# power_management.net
KiCad netlist of a schematic drawn in Altium Designer
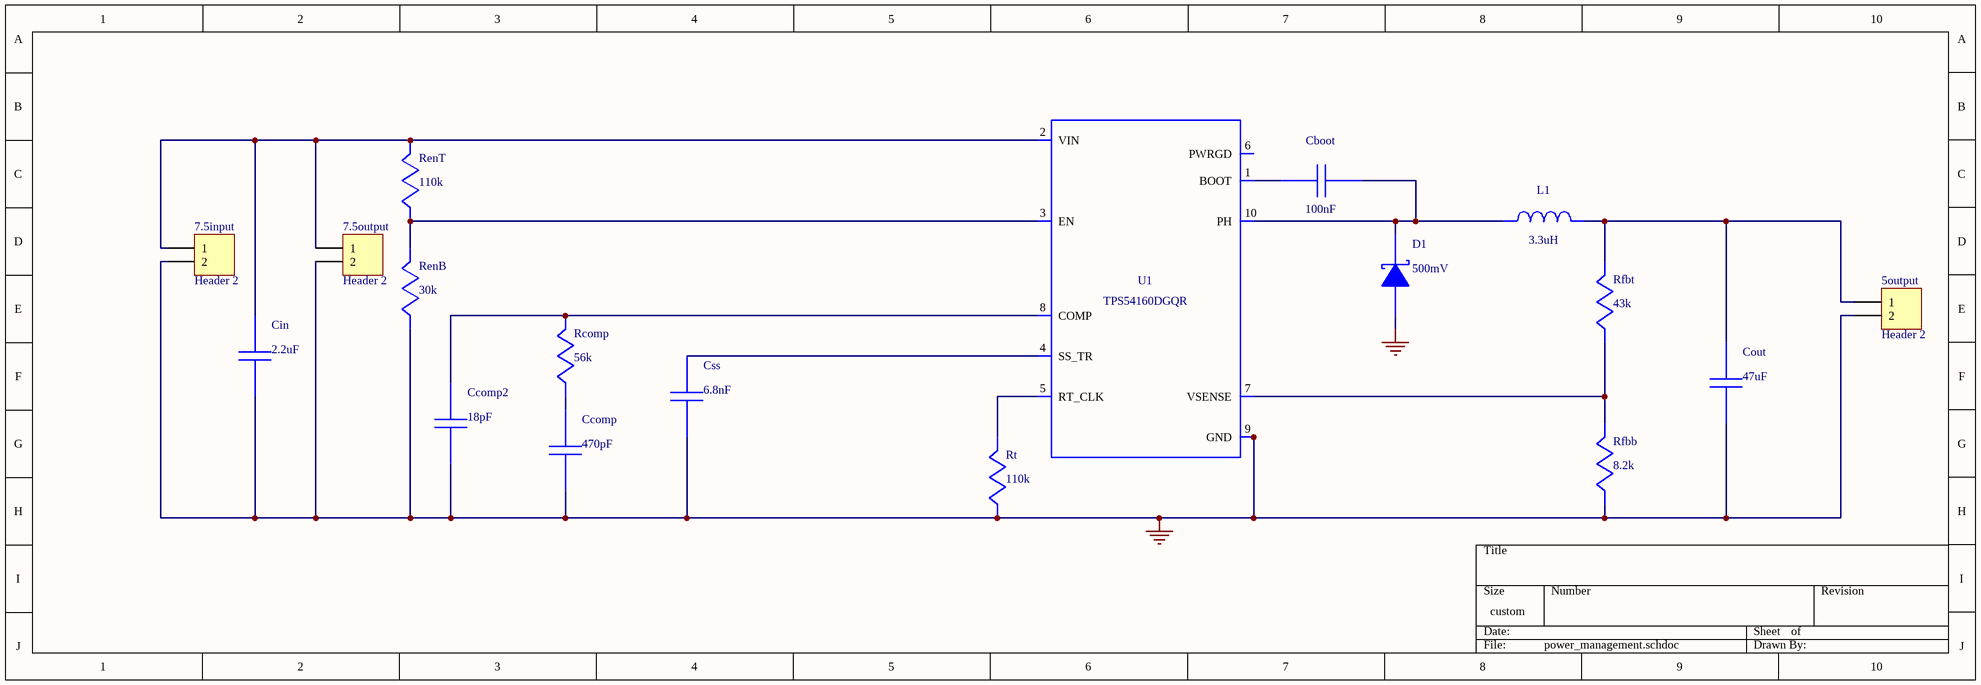
[diagram p0: power_management.schdoc]

(export (version "E")
  (design (tool "Eeschema 10.0.6"))
  (components
    (comp (ref "5output")
      (value "Header 2")
      (footprint "HDR1X2")
      (description "Header, 2-Pin")
      (fields (field (name "PUBLISHER") "Altium Limited"))
      (libsource (lib "Miscellaneous Connectors") (part "Header 2"))
    )
    (comp (ref "7.5input")
      (value "Header 2")
      (footprint "HDR1X2")
      (description "Header, 2-Pin")
      (fields (field (name "PUBLISHER") "Altium Limited"))
      (libsource (lib "Miscellaneous Connectors") (part "Header 2"))
    )
    (comp (ref "7.5output")
      (value "Header 2")
      (footprint "HDR1X2")
      (description "Header, 2-Pin")
      (fields (field (name "PUBLISHER") "Altium Limited"))
      (libsource (lib "Miscellaneous Connectors") (part "Header 2"))
    )
    (comp (ref "Cboot")
      (value "100nF")
      (footprint "RAD-0.2")
      (description "GRM155R61A104KA0")
      (fields (field (name "MANUFACTURER PART NUMBER") "GRM155R61A104KA01D"))
      (libsource (lib "TI WEBENCH") (part "Cboot"))
    )
    (comp (ref "Ccomp")
      (value "470pF")
      (footprint "RAD-0.2")
      (description "CC0805KRX7R9BB47")
      (fields (field (name "MANUFACTURER PART NUMBER") "CC0805KRX7R9BB471"))
      (libsource (lib "TI WEBENCH") (part "Ccomp"))
    )
    (comp (ref "Ccomp2")
      (value "18pF")
      (footprint "RAD-0.1")
      (description "C0805C180K5GACTU")
      (libsource (lib "TI WEBENCH") (part "Ccomp2"))
    )
    (comp (ref "Cin")
      (value "2.2uF")
      (footprint "CAPR5-4X5")
      (description "GRM188R61A225KE3")
      (fields (field (name "MANUFACTURER PART NUMBER") "GRM188R61A225KE34D"))
      (libsource (lib "TI WEBENCH") (part "Cin"))
    )
    (comp (ref "Cout")
      (value "47uF")
      (footprint "CAPR5-4X5")
      (description "C2012X5R1A476M12")
      (fields (field (name "MANUFACTURER PART NUMBER") "C2012X5R1A476M125AC"))
      (libsource (lib "TI WEBENCH") (part "Cout"))
    )
    (comp (ref "Css")
      (value "6.8nF")
      (footprint "RAD-0.1")
      (description "CC0805KRX7R9BB68")
      (fields (field (name "MANUFACTURER PART NUMBER") "CC0805KRX7R9BB682"))
      (libsource (lib "TI WEBENCH") (part "Css"))
    )
    (comp (ref "D1")
      (value "500mV")
      (footprint "DIODE-0.7")
      (description "B340A-13-F")
      (libsource (lib "TI WEBENCH") (part "D1"))
    )
    (comp (ref "L1")
      (value "3.3uH")
      (footprint "AXIAL-0.4")
      (description "SRN6045-3R3Y")
      (libsource (lib "TI WEBENCH") (part "L1"))
    )
    (comp (ref "Rcomp")
      (value "56k")
      (footprint "AXIAL-0.4")
      (description "RC1206FR-0756KL")
      (libsource (lib "TI WEBENCH") (part "Rcomp"))
    )
    (comp (ref "RenB")
      (value "30k")
      (footprint "AXIAL-0.4")
      (description "RC1206FR-0730KL")
      (libsource (lib "TI WEBENCH") (part "RenB"))
    )
    (comp (ref "RenT")
      (value "110k")
      (footprint "AXIAL-0.4")
      (description "ERJ-8ENF1103V")
      (libsource (lib "TI WEBENCH") (part "RenT"))
    )
    (comp (ref "Rfbb")
      (value "8.2k")
      (footprint "AXIAL-0.4")
      (description "RC1206FR-078K2L")
      (libsource (lib "TI WEBENCH") (part "Rfbb"))
    )
    (comp (ref "Rfbt")
      (value "43k")
      (footprint "AXIAL-0.4")
      (description "RC1206FR-0743KL")
      (libsource (lib "TI WEBENCH") (part "Rfbt"))
    )
    (comp (ref "Rt")
      (value "110k")
      (footprint "AXIAL-0.4")
      (description "CRCW1206110KFKEA")
      (libsource (lib "TI WEBENCH") (part "Rt"))
    )
    (comp (ref "U1")
      (value "TPS54140DGQR")
      (footprint "Miscellaneous Devices:N10A")
      (description "TPS54160DGQR")
      (fields (field (name "PACKAGEREFERENCE") "TPS54160DGQR"))
      (libsource (lib "TI WEBENCH") (part "U1"))
    )
  )
  (nets
    (net (code "1") (name "0") (class "Default")
      (node (ref "5output") (pin "2") (pinfunction "2_2") (pintype "passive"))
      (node (ref "7.5input") (pin "2") (pinfunction "2_2") (pintype "passive"))
      (node (ref "7.5output") (pin "2") (pinfunction "2_2") (pintype "passive"))
      (node (ref "Ccomp") (pin "2") (pinfunction "2_2") (pintype "passive"))
      (node (ref "Ccomp2") (pin "2") (pinfunction "2_2") (pintype "passive"))
      (node (ref "Cin") (pin "2") (pinfunction "2_2") (pintype "passive"))
      (node (ref "Cout") (pin "2") (pinfunction "2_2") (pintype "passive"))
      (node (ref "Css") (pin "2") (pinfunction "2_2") (pintype "passive"))
      (node (ref "D1") (pin "2") (pinfunction "A_2") (pintype "passive"))
      (node (ref "RenB") (pin "2") (pinfunction "2_2") (pintype "passive"))
      (node (ref "Rfbb") (pin "2") (pinfunction "2_2") (pintype "passive"))
      (node (ref "Rt") (pin "2") (pinfunction "2_2") (pintype "passive"))
      (node (ref "U1") (pin "11") (pinfunction "EPAD_11") (pintype "passive"))
      (node (ref "U1") (pin "9") (pinfunction "GND_9") (pintype "passive"))
    )
    (net (code "2") (name "Net-(5output-Pad1)") (class "Default")
      (node (ref "5output") (pin "1") (pinfunction "1_1") (pintype "passive"))
      (node (ref "Cout") (pin "1") (pinfunction "1_1") (pintype "passive"))
      (node (ref "L1") (pin "1") (pinfunction "1_1") (pintype "passive"))
      (node (ref "Rfbt") (pin "1") (pinfunction "1_1") (pintype "passive"))
    )
    (net (code "3") (name "Net-(Ccomp-Pad1)") (class "Default")
      (node (ref "Ccomp") (pin "1") (pinfunction "1_1") (pintype "passive"))
      (node (ref "Rcomp") (pin "2") (pinfunction "2_2") (pintype "passive"))
    )
    (net (code "4") (name "Net-(D1-K)") (class "Default")
      (node (ref "Cboot") (pin "2") (pinfunction "2_2") (pintype "passive"))
      (node (ref "D1") (pin "1") (pinfunction "K_1") (pintype "passive"))
      (node (ref "L1") (pin "2") (pinfunction "2_2") (pintype "passive"))
      (node (ref "U1") (pin "10") (pinfunction "PH_10") (pintype "passive"))
    )
    (net (code "5") (name "Net-(U1-BOOT)") (class "Default")
      (node (ref "Cboot") (pin "1") (pinfunction "1_1") (pintype "passive"))
      (node (ref "U1") (pin "1") (pinfunction "BOOT_1") (pintype "passive"))
    )
    (net (code "6") (name "Net-(U1-COMP)") (class "Default")
      (node (ref "Ccomp2") (pin "1") (pinfunction "1_1") (pintype "passive"))
      (node (ref "Rcomp") (pin "1") (pinfunction "1_1") (pintype "passive"))
      (node (ref "U1") (pin "8") (pinfunction "COMP_8") (pintype "passive"))
    )
    (net (code "7") (name "Net-(U1-EN)") (class "Default")
      (node (ref "RenB") (pin "1") (pinfunction "1_1") (pintype "passive"))
      (node (ref "RenT") (pin "2") (pinfunction "2_2") (pintype "passive"))
      (node (ref "U1") (pin "3") (pinfunction "EN_3") (pintype "passive"))
    )
    (net (code "8") (name "Net-(U1-RT_CLK)") (class "Default")
      (node (ref "Rt") (pin "1") (pinfunction "1_1") (pintype "passive"))
      (node (ref "U1") (pin "5") (pinfunction "RT_CLK_5") (pintype "passive"))
    )
    (net (code "9") (name "Net-(U1-SS_TR)") (class "Default")
      (node (ref "Css") (pin "1") (pinfunction "1_1") (pintype "passive"))
      (node (ref "U1") (pin "4") (pinfunction "SS_TR_4") (pintype "passive"))
    )
    (net (code "10") (name "Net-(U1-VIN)") (class "Default")
      (node (ref "7.5input") (pin "1") (pinfunction "1_1") (pintype "passive"))
      (node (ref "7.5output") (pin "1") (pinfunction "1_1") (pintype "passive"))
      (node (ref "Cin") (pin "1") (pinfunction "1_1") (pintype "passive"))
      (node (ref "RenT") (pin "1") (pinfunction "1_1") (pintype "passive"))
      (node (ref "U1") (pin "2") (pinfunction "VIN_2") (pintype "passive"))
    )
    (net (code "11") (name "Net-(U1-VSENSE)") (class "Default")
      (node (ref "Rfbb") (pin "1") (pinfunction "1_1") (pintype "passive"))
      (node (ref "Rfbt") (pin "2") (pinfunction "2_2") (pintype "passive"))
      (node (ref "U1") (pin "7") (pinfunction "VSENSE_7") (pintype "passive"))
    )
    (net (code "12") (name "unconnected-(U1-PWRGD-Pad6)") (class "Default")
      (node (ref "U1") (pin "6") (pinfunction "PWRGD_6") (pintype "passive"))
    )
  )
)
